# PROCESSOR.net
KiCad netlist of a schematic drawn in Altium Designer
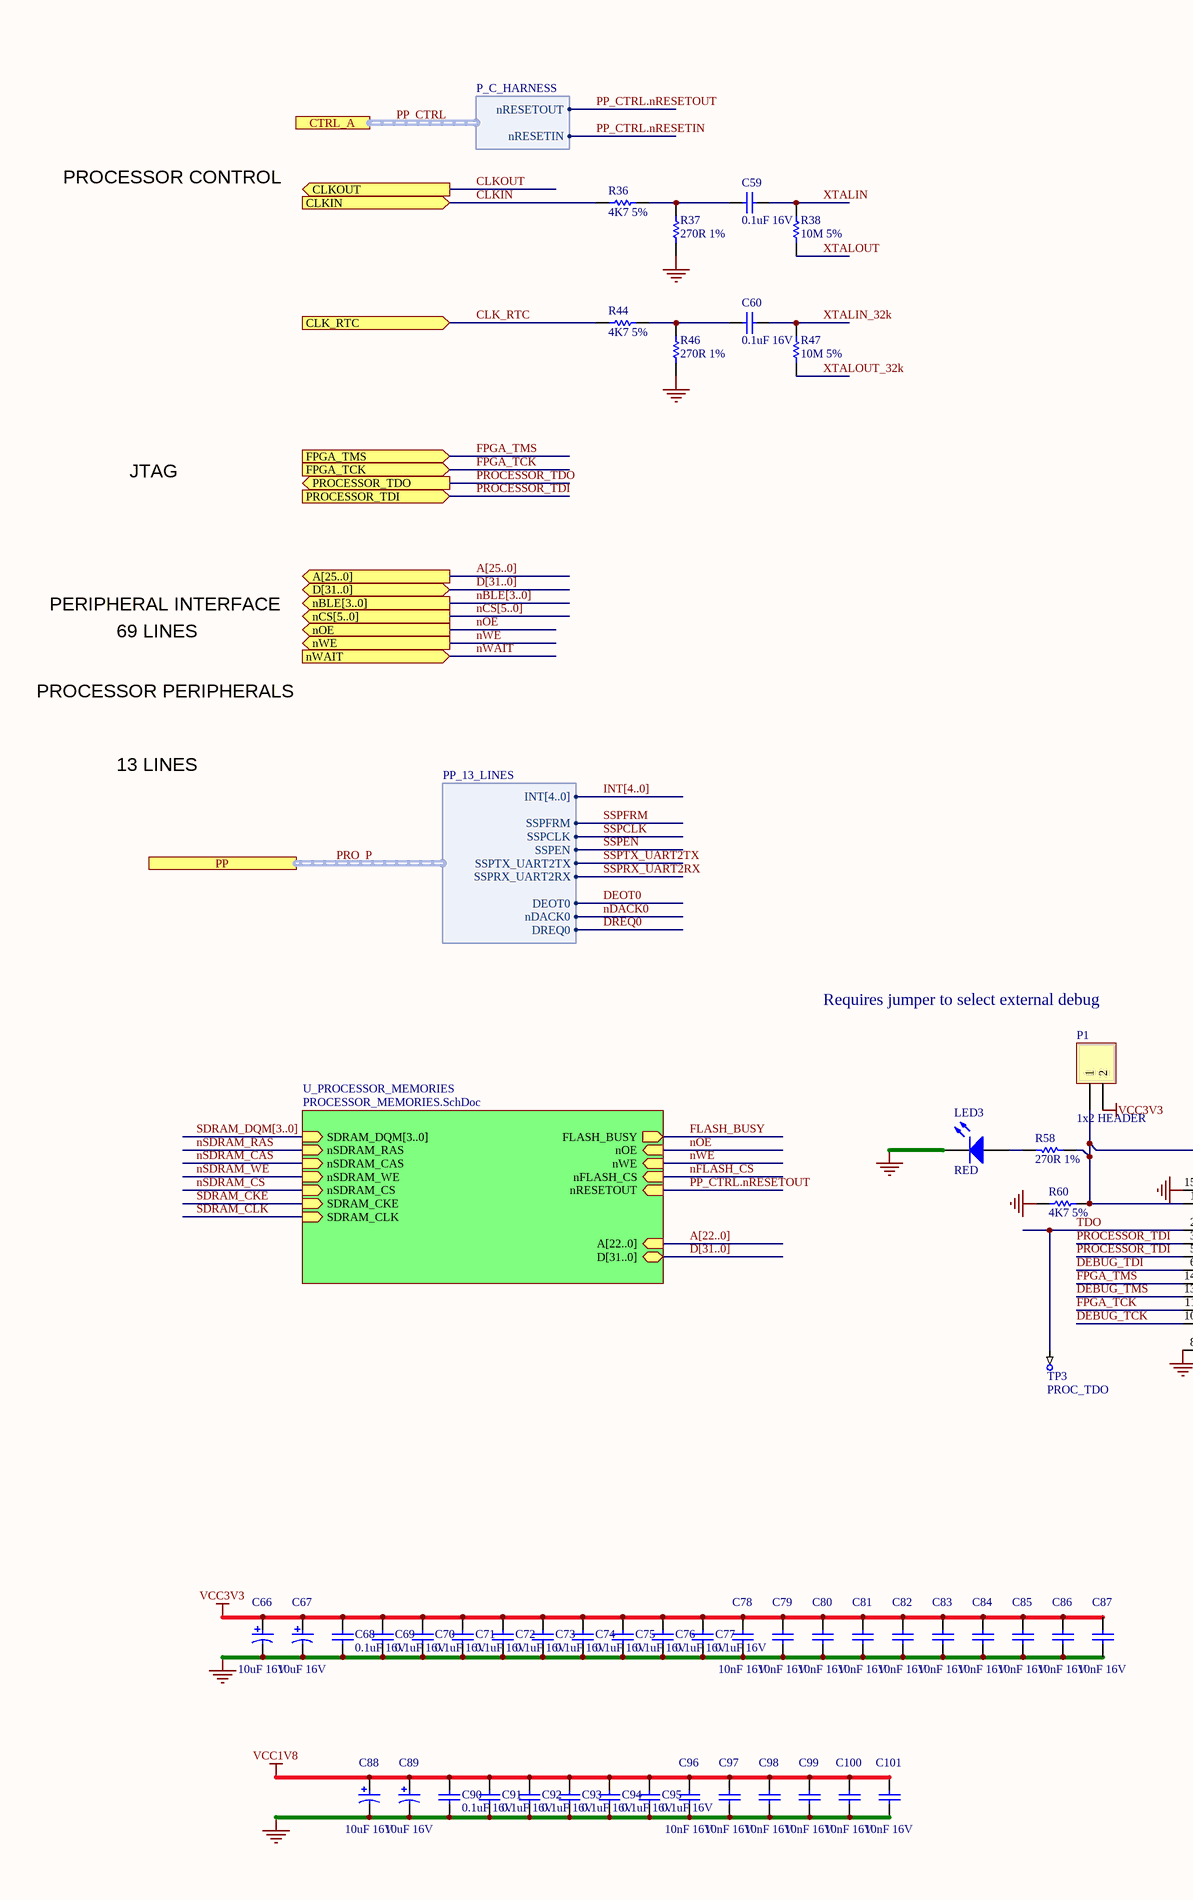
[diagram p0: PROCESSOR.SchDoc, left]
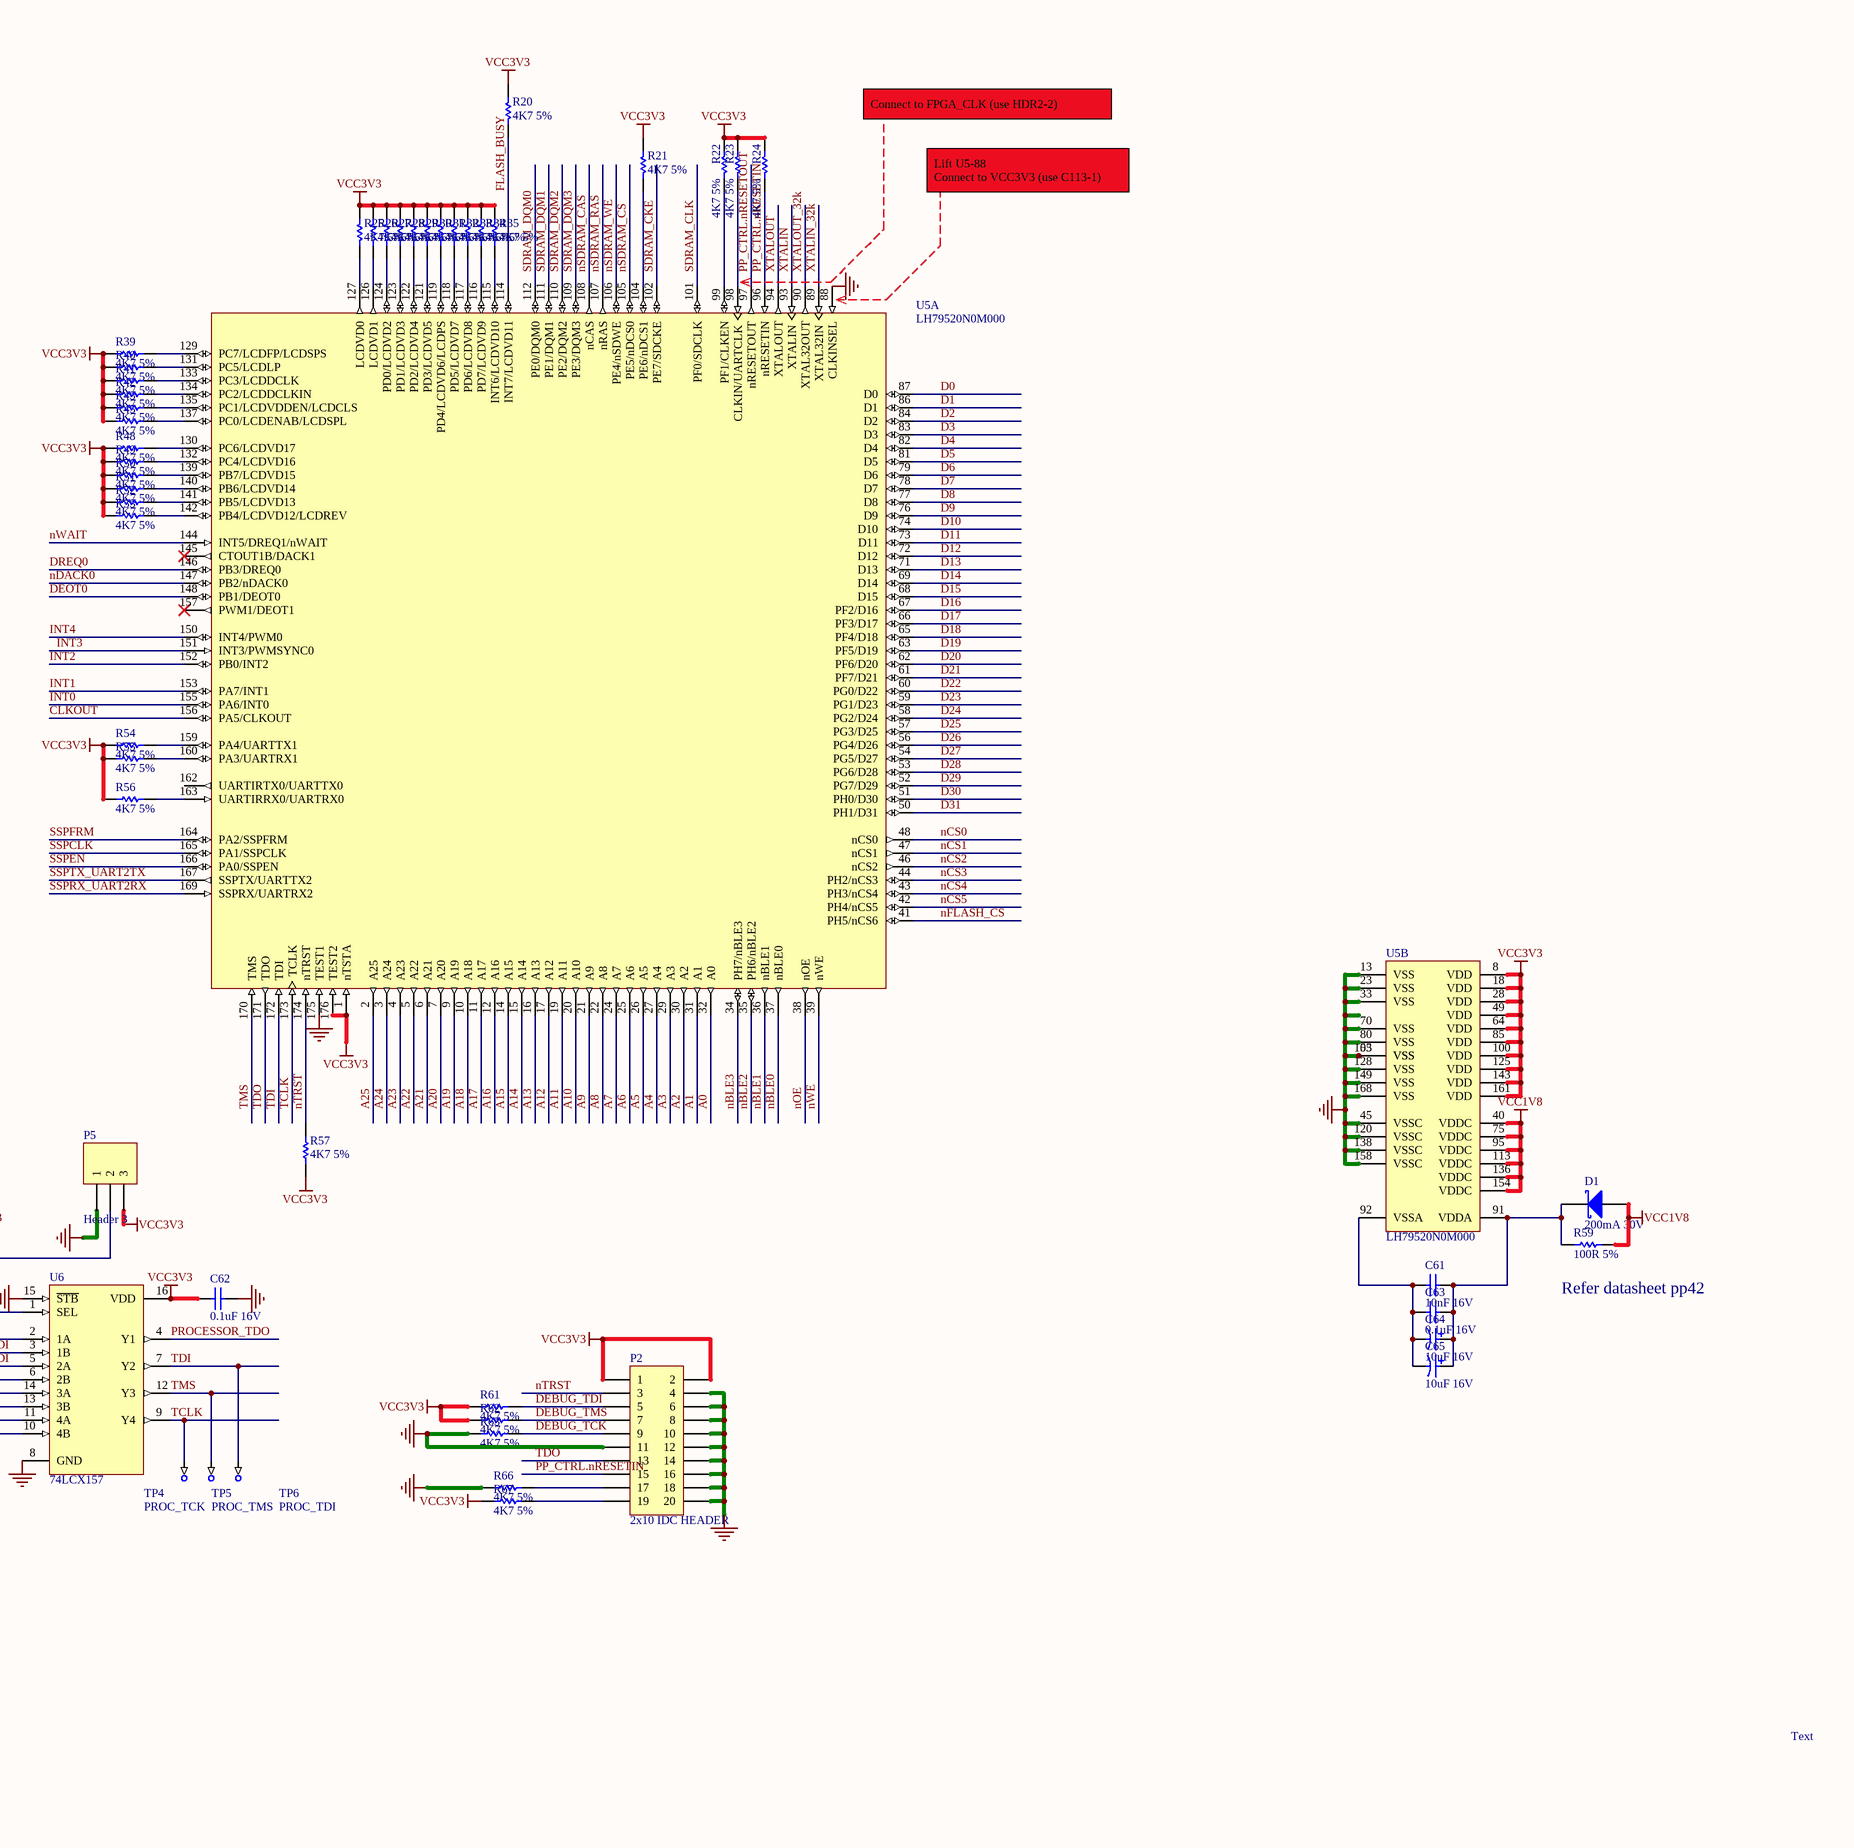
[diagram p1: PROCESSOR.SchDoc, right]

(export (version "E")
  (design (tool "Eeschema 10.0.6"))
  (components
    (comp (ref "C59")
      (value "0.1uF 16V")
      (footprint "CAPC1005")
      (description "Capacitor")
      (libsource (lib "Altium Design Library") (part "CAP-NP"))
    )
    (comp (ref "C60")
      (value "0.1uF 16V")
      (footprint "CAPC1005")
      (description "Capacitor")
      (libsource (lib "Altium Design Library") (part "CAP-NP"))
    )
    (comp (ref "C61")
      (value "10nF 16V")
      (footprint "CAPC1005")
      (description "Capacitor")
      (libsource (lib "Altium Design Library") (part "CAP-NP"))
    )
    (comp (ref "C62")
      (value "0.1uF 16V")
      (footprint "CAPC1005")
      (description "Capacitor")
      (libsource (lib "Altium Design Library") (part "CAP-NP"))
    )
    (comp (ref "C63")
      (value "0.1uF 16V")
      (footprint "CAPC1005")
      (description "Capacitor")
      (libsource (lib "Altium Design Library") (part "CAP-NP"))
    )
    (comp (ref "C64")
      (value "10uF 16V")
      (footprint "CAPC3528")
      (description "Polar Capacitor")
      (libsource (lib "Altium Design Library") (part "CAP-P"))
    )
    (comp (ref "C65")
      (value "10uF 16V")
      (footprint "CAPC3528")
      (description "Polar Capacitor")
      (libsource (lib "Altium Design Library") (part "CAP-P"))
    )
    (comp (ref "C66")
      (value "10uF 16V")
      (footprint "CAPC3528")
      (description "Polar Capacitor")
      (libsource (lib "Altium Design Library") (part "CAP-P"))
    )
    (comp (ref "C67")
      (value "10uF 16V")
      (footprint "CAPC3528")
      (description "Polar Capacitor")
      (libsource (lib "Altium Design Library") (part "CAP-P"))
    )
    (comp (ref "C68")
      (value "0.1uF 16V")
      (footprint "CAPC1005")
      (description "Capacitor")
      (libsource (lib "Altium Design Library") (part "CAP-NP"))
    )
    (comp (ref "C69")
      (value "0.1uF 16V")
      (footprint "CAPC1005")
      (description "Capacitor")
      (libsource (lib "Altium Design Library") (part "CAP-NP"))
    )
    (comp (ref "C70")
      (value "0.1uF 16V")
      (footprint "CAPC1005")
      (description "Capacitor")
      (libsource (lib "Altium Design Library") (part "CAP-NP"))
    )
    (comp (ref "C71")
      (value "0.1uF 16V")
      (footprint "CAPC1005")
      (description "Capacitor")
      (libsource (lib "Altium Design Library") (part "CAP-NP"))
    )
    (comp (ref "C72")
      (value "0.1uF 16V")
      (footprint "CAPC1005")
      (description "Capacitor")
      (libsource (lib "Altium Design Library") (part "CAP-NP"))
    )
    (comp (ref "C73")
      (value "0.1uF 16V")
      (footprint "CAPC1005")
      (description "Capacitor")
      (libsource (lib "Altium Design Library") (part "CAP-NP"))
    )
    (comp (ref "C74")
      (value "0.1uF 16V")
      (footprint "CAPC1005")
      (description "Capacitor")
      (libsource (lib "Altium Design Library") (part "CAP-NP"))
    )
    (comp (ref "C75")
      (value "0.1uF 16V")
      (footprint "CAPC1005")
      (description "Capacitor")
      (libsource (lib "Altium Design Library") (part "CAP-NP"))
    )
    (comp (ref "C76")
      (value "0.1uF 16V")
      (footprint "CAPC1005")
      (description "Capacitor")
      (libsource (lib "Altium Design Library") (part "CAP-NP"))
    )
    (comp (ref "C77")
      (value "0.1uF 16V")
      (footprint "CAPC1005")
      (description "Capacitor")
      (libsource (lib "Altium Design Library") (part "CAP-NP"))
    )
    (comp (ref "C78")
      (value "10nF 16V")
      (footprint "CAPC1005")
      (description "Capacitor")
      (libsource (lib "Altium Design Library") (part "CAP-NP"))
    )
    (comp (ref "C79")
      (value "10nF 16V")
      (footprint "CAPC1005")
      (description "Capacitor")
      (libsource (lib "Altium Design Library") (part "CAP-NP"))
    )
    (comp (ref "C80")
      (value "10nF 16V")
      (footprint "CAPC1005")
      (description "Capacitor")
      (libsource (lib "Altium Design Library") (part "CAP-NP"))
    )
    (comp (ref "C81")
      (value "10nF 16V")
      (footprint "CAPC1005")
      (description "Capacitor")
      (libsource (lib "Altium Design Library") (part "CAP-NP"))
    )
    (comp (ref "C82")
      (value "10nF 16V")
      (footprint "CAPC1005")
      (description "Capacitor")
      (libsource (lib "Altium Design Library") (part "CAP-NP"))
    )
    (comp (ref "C83")
      (value "10nF 16V")
      (footprint "CAPC1005")
      (description "Capacitor")
      (libsource (lib "Altium Design Library") (part "CAP-NP"))
    )
    (comp (ref "C84")
      (value "10nF 16V")
      (footprint "CAPC1005")
      (description "Capacitor")
      (libsource (lib "Altium Design Library") (part "CAP-NP"))
    )
    (comp (ref "C85")
      (value "10nF 16V")
      (footprint "CAPC1005")
      (description "Capacitor")
      (libsource (lib "Altium Design Library") (part "CAP-NP"))
    )
    (comp (ref "C86")
      (value "10nF 16V")
      (footprint "CAPC1005")
      (description "Capacitor")
      (libsource (lib "Altium Design Library") (part "CAP-NP"))
    )
    (comp (ref "C87")
      (value "10nF 16V")
      (footprint "CAPC1005")
      (description "Capacitor")
      (libsource (lib "Altium Design Library") (part "CAP-NP"))
    )
    (comp (ref "C88")
      (value "10uF 16V")
      (footprint "CAPC3528")
      (description "Polar Capacitor")
      (libsource (lib "Altium Design Library") (part "CAP-P"))
    )
    (comp (ref "C89")
      (value "10uF 16V")
      (footprint "CAPC3528")
      (description "Polar Capacitor")
      (libsource (lib "Altium Design Library") (part "CAP-P"))
    )
    (comp (ref "C90")
      (value "0.1uF 16V")
      (footprint "CAPC1005")
      (description "Capacitor")
      (libsource (lib "Altium Design Library") (part "CAP-NP"))
    )
    (comp (ref "C91")
      (value "0.1uF 16V")
      (footprint "CAPC1005")
      (description "Capacitor")
      (libsource (lib "Altium Design Library") (part "CAP-NP"))
    )
    (comp (ref "C92")
      (value "0.1uF 16V")
      (footprint "CAPC1005")
      (description "Capacitor")
      (libsource (lib "Altium Design Library") (part "CAP-NP"))
    )
    (comp (ref "C93")
      (value "0.1uF 16V")
      (footprint "CAPC1005")
      (description "Capacitor")
      (libsource (lib "Altium Design Library") (part "CAP-NP"))
    )
    (comp (ref "C94")
      (value "0.1uF 16V")
      (footprint "CAPC1005")
      (description "Capacitor")
      (libsource (lib "Altium Design Library") (part "CAP-NP"))
    )
    (comp (ref "C95")
      (value "0.1uF 16V")
      (footprint "CAPC1005")
      (description "Capacitor")
      (libsource (lib "Altium Design Library") (part "CAP-NP"))
    )
    (comp (ref "C96")
      (value "10nF 16V")
      (footprint "CAPC1005")
      (description "Capacitor")
      (libsource (lib "Altium Design Library") (part "CAP-NP"))
    )
    (comp (ref "C97")
      (value "10nF 16V")
      (footprint "CAPC1005")
      (description "Capacitor")
      (libsource (lib "Altium Design Library") (part "CAP-NP"))
    )
    (comp (ref "C98")
      (value "10nF 16V")
      (footprint "CAPC1005")
      (description "Capacitor")
      (libsource (lib "Altium Design Library") (part "CAP-NP"))
    )
    (comp (ref "C99")
      (value "10nF 16V")
      (footprint "CAPC1005")
      (description "Capacitor")
      (libsource (lib "Altium Design Library") (part "CAP-NP"))
    )
    (comp (ref "C100")
      (value "10nF 16V")
      (footprint "CAPC1005")
      (description "Capacitor")
      (libsource (lib "Altium Design Library") (part "CAP-NP"))
    )
    (comp (ref "C101")
      (value "10nF 16V")
      (footprint "CAPC1005")
      (description "Capacitor")
      (libsource (lib "Altium Design Library") (part "CAP-NP"))
    )
    (comp (ref "D1")
      (value "200mA 30V")
      (footprint "SOT95P230-3")
      (description "Schottky Barrier Double Diode")
      (libsource (lib "Altium Design Library") (part "DIO-SCHOTTKY-1S-SOT23"))
    )
    (comp (ref "LED3")
      (value "RED")
      (footprint "LED2013")
      (description "Typical GREEN SMD LED Agilent make")
      (libsource (lib "Altium Design Library") (part "DIO-LED-1S"))
    )
    (comp (ref "P1")
      (value "1x2 HEADER")
      (footprint "HDR1X2")
      (description "Header, 2-Pin")
      (libsource (lib "Altium Design Library") (part "CON-HDR-1x2-STR"))
    )
    (comp (ref "P2")
      (value "2x10 IDC HEADER")
      (footprint "IDC2.54-V20D")
      (description "10x2 IDC Male PCB Box Header")
      (libsource (lib "Altium Design Library") (part "CON-IDC-2x10-M-STR"))
    )
    (comp (ref "P5")
      (value "Header 3")
      (footprint "HDR1X3")
      (description "Header, 3-Pin")
      (fields (field (name "PUBLISHER") "Altium Limited"))
      (libsource (lib "Miscellaneous Connectors") (part "Header 3"))
    )
    (comp (ref "R20")
      (value "4K7 5%")
      (footprint "RESC1005")
      (description "Resistor")
      (libsource (lib "Altium Design Library") (part "RES"))
    )
    (comp (ref "R21")
      (value "4K7 5%")
      (footprint "RESC1005")
      (description "Resistor")
      (libsource (lib "Altium Design Library") (part "RES"))
    )
    (comp (ref "R22")
      (value "4K7 5%")
      (footprint "RESC1005")
      (description "Resistor")
      (libsource (lib "Altium Design Library") (part "RES"))
    )
    (comp (ref "R23")
      (value "4K7 5%")
      (footprint "RESC1005")
      (description "Resistor")
      (libsource (lib "Altium Design Library") (part "RES"))
    )
    (comp (ref "R24")
      (value "4K7 5%")
      (footprint "RESC1005")
      (description "Resistor")
      (libsource (lib "Altium Design Library") (part "RES"))
    )
    (comp (ref "R25")
      (value "4K7 5%")
      (footprint "RESC1005")
      (description "Resistor")
      (libsource (lib "Altium Design Library") (part "RES"))
    )
    (comp (ref "R26")
      (value "4K7 5%")
      (footprint "RESC1005")
      (description "Resistor")
      (libsource (lib "Altium Design Library") (part "RES"))
    )
    (comp (ref "R27")
      (value "4K7 5%")
      (footprint "RESC1005")
      (description "Resistor")
      (libsource (lib "Altium Design Library") (part "RES"))
    )
    (comp (ref "R28")
      (value "4K7 5%")
      (footprint "RESC1005")
      (description "Resistor")
      (libsource (lib "Altium Design Library") (part "RES"))
    )
    (comp (ref "R29")
      (value "4K7 5%")
      (footprint "RESC1005")
      (description "Resistor")
      (libsource (lib "Altium Design Library") (part "RES"))
    )
    (comp (ref "R30")
      (value "4K7 5%")
      (footprint "RESC1005")
      (description "Resistor")
      (libsource (lib "Altium Design Library") (part "RES"))
    )
    (comp (ref "R31")
      (value "4K7 5%")
      (footprint "RESC1005")
      (description "Resistor")
      (libsource (lib "Altium Design Library") (part "RES"))
    )
    (comp (ref "R32")
      (value "4K7 5%")
      (footprint "RESC1005")
      (description "Resistor")
      (libsource (lib "Altium Design Library") (part "RES"))
    )
    (comp (ref "R33")
      (value "4K7 5%")
      (footprint "RESC1005")
      (description "Resistor")
      (libsource (lib "Altium Design Library") (part "RES"))
    )
    (comp (ref "R34")
      (value "4K7 5%")
      (footprint "RESC1005")
      (description "Resistor")
      (libsource (lib "Altium Design Library") (part "RES"))
    )
    (comp (ref "R35")
      (value "4K7 5%")
      (footprint "RESC1005")
      (description "Resistor")
      (libsource (lib "Altium Design Library") (part "RES"))
    )
    (comp (ref "R36")
      (value "4K7 5%")
      (footprint "RESC1005")
      (description "Resistor")
      (libsource (lib "Altium Design Library") (part "RES"))
    )
    (comp (ref "R37")
      (value "270R 1%")
      (footprint "RESC2012")
      (description "Resistor")
      (libsource (lib "Altium Design Library") (part "RES"))
    )
    (comp (ref "R38")
      (value "10M 5%")
      (footprint "RESC2012")
      (description "Resistor")
      (libsource (lib "Altium Design Library") (part "RES"))
    )
    (comp (ref "R39")
      (value "4K7 5%")
      (footprint "RESC1005")
      (description "Resistor")
      (libsource (lib "Altium Design Library") (part "RES"))
    )
    (comp (ref "R40")
      (value "4K7 5%")
      (footprint "RESC1005")
      (description "Resistor")
      (libsource (lib "Altium Design Library") (part "RES"))
    )
    (comp (ref "R41")
      (value "4K7 5%")
      (footprint "RESC1005")
      (description "Resistor")
      (libsource (lib "Altium Design Library") (part "RES"))
    )
    (comp (ref "R42")
      (value "4K7 5%")
      (footprint "RESC1005")
      (description "Resistor")
      (libsource (lib "Altium Design Library") (part "RES"))
    )
    (comp (ref "R43")
      (value "4K7 5%")
      (footprint "RESC1005")
      (description "Resistor")
      (libsource (lib "Altium Design Library") (part "RES"))
    )
    (comp (ref "R44")
      (value "4K7 5%")
      (footprint "RESC1005")
      (description "Resistor")
      (libsource (lib "Altium Design Library") (part "RES"))
    )
    (comp (ref "R45")
      (value "4K7 5%")
      (footprint "RESC1005")
      (description "Resistor")
      (libsource (lib "Altium Design Library") (part "RES"))
    )
    (comp (ref "R46")
      (value "270R 1%")
      (footprint "RESC2012")
      (description "Resistor")
      (libsource (lib "Altium Design Library") (part "RES"))
    )
    (comp (ref "R47")
      (value "10M 5%")
      (footprint "RESC2012")
      (description "Resistor")
      (libsource (lib "Altium Design Library") (part "RES"))
    )
    (comp (ref "R48")
      (value "4K7 5%")
      (footprint "RESC1005")
      (description "Resistor")
      (libsource (lib "Altium Design Library") (part "RES"))
    )
    (comp (ref "R49")
      (value "4K7 5%")
      (footprint "RESC1005")
      (description "Resistor")
      (libsource (lib "Altium Design Library") (part "RES"))
    )
    (comp (ref "R50")
      (value "4K7 5%")
      (footprint "RESC1005")
      (description "Resistor")
      (libsource (lib "Altium Design Library") (part "RES"))
    )
    (comp (ref "R51")
      (value "4K7 5%")
      (footprint "RESC1005")
      (description "Resistor")
      (libsource (lib "Altium Design Library") (part "RES"))
    )
    (comp (ref "R52")
      (value "4K7 5%")
      (footprint "RESC1005")
      (description "Resistor")
      (libsource (lib "Altium Design Library") (part "RES"))
    )
    (comp (ref "R53")
      (value "4K7 5%")
      (footprint "RESC1005")
      (description "Resistor")
      (libsource (lib "Altium Design Library") (part "RES"))
    )
    (comp (ref "R54")
      (value "4K7 5%")
      (footprint "RESC1005")
      (description "Resistor")
      (libsource (lib "Altium Design Library") (part "RES"))
    )
    (comp (ref "R55")
      (value "4K7 5%")
      (footprint "RESC1005")
      (description "Resistor")
      (libsource (lib "Altium Design Library") (part "RES"))
    )
    (comp (ref "R56")
      (value "4K7 5%")
      (footprint "RESC1005")
      (description "Resistor")
      (libsource (lib "Altium Design Library") (part "RES"))
    )
    (comp (ref "R57")
      (value "4K7 5%")
      (footprint "RESC1005")
      (description "Resistor")
      (libsource (lib "Altium Design Library") (part "RES"))
    )
    (comp (ref "R58")
      (value "270R 1%")
      (footprint "RESC2012")
      (description "Resistor")
      (libsource (lib "Altium Design Library") (part "RES"))
    )
    (comp (ref "R59")
      (value "100R 5%")
      (footprint "RESC2012")
      (description "Resistor")
      (libsource (lib "Altium Design Library") (part "RES"))
    )
    (comp (ref "R60")
      (value "4K7 5%")
      (footprint "RESC1005")
      (description "Resistor")
      (libsource (lib "Altium Design Library") (part "RES"))
    )
    (comp (ref "R61")
      (value "4K7 5%")
      (footprint "RESC1005")
      (description "Resistor")
      (libsource (lib "Altium Design Library") (part "RES"))
    )
    (comp (ref "R62")
      (value "4K7 5%")
      (footprint "RESC1005")
      (description "Resistor")
      (libsource (lib "Altium Design Library") (part "RES"))
    )
    (comp (ref "R63")
      (value "4K7 5%")
      (footprint "RESC1005")
      (description "Resistor")
      (libsource (lib "Altium Design Library") (part "RES"))
    )
    (comp (ref "R66")
      (value "4K7 5%")
      (footprint "RESC1005")
      (description "Resistor")
      (libsource (lib "Altium Design Library") (part "RES"))
    )
    (comp (ref "R67")
      (value "4K7 5%")
      (footprint "RESC1005")
      (description "Resistor")
      (libsource (lib "Altium Design Library") (part "RES"))
    )
    (comp (ref "TP3")
      (value "PROC_TDO")
      (footprint "TestPin")
      (libsource (lib "Altium Design Library") (part "TestPin"))
    )
    (comp (ref "TP4")
      (value "PROC_TCK")
      (footprint "TestPin")
      (libsource (lib "Altium Design Library") (part "TestPin"))
    )
    (comp (ref "TP5")
      (value "PROC_TMS")
      (footprint "TestPin")
      (libsource (lib "Altium Design Library") (part "TestPin"))
    )
    (comp (ref "TP6")
      (value "PROC_TDI")
      (footprint "TestPin")
      (libsource (lib "Altium Design Library") (part "TestPin"))
    )
    (comp (ref "U5")
      (value "LH79520N0M000")
      (footprint "QFP40P2000X2000-176")
      (libsource (lib "Altium Design Library") (part "LH79520N0M000"))
    )
    (comp (ref "U6")
      (value "74LCX157")
      (footprint "TSOP65P638-16")
      (description "Quad 2-Input Multiplexer")
      (libsource (lib "Altium Design Library") (part "74LCX157-TSOP16"))
    )
  )
  (nets
    (net (code "3") (name "/A0") (class "Default")
      (node (ref "U5") (pin "32") (pinfunction "A0_32") (pintype "output"))
    )
    (net (code "4") (name "/A1") (class "Default")
      (node (ref "U5") (pin "31") (pinfunction "A1_31") (pintype "output"))
    )
    (net (code "5") (name "/A2") (class "Default")
      (node (ref "U5") (pin "30") (pinfunction "A2_30") (pintype "output"))
    )
    (net (code "6") (name "/A3") (class "Default")
      (node (ref "U5") (pin "29") (pinfunction "A3_29") (pintype "output"))
    )
    (net (code "7") (name "/A4") (class "Default")
      (node (ref "U5") (pin "27") (pinfunction "A4_27") (pintype "output"))
    )
    (net (code "8") (name "/A5") (class "Default")
      (node (ref "U5") (pin "26") (pinfunction "A5_26") (pintype "output"))
    )
    (net (code "9") (name "/A6") (class "Default")
      (node (ref "U5") (pin "25") (pinfunction "A6_25") (pintype "output"))
    )
    (net (code "10") (name "/A7") (class "Default")
      (node (ref "U5") (pin "24") (pinfunction "A7_24") (pintype "output"))
    )
    (net (code "11") (name "/A8") (class "Default")
      (node (ref "U5") (pin "22") (pinfunction "A8_22") (pintype "output"))
    )
    (net (code "12") (name "/A9") (class "Default")
      (node (ref "U5") (pin "21") (pinfunction "A9_21") (pintype "output"))
    )
    (net (code "13") (name "/A10") (class "Default")
      (node (ref "U5") (pin "20") (pinfunction "A10_20") (pintype "output"))
    )
    (net (code "14") (name "/A11") (class "Default")
      (node (ref "U5") (pin "19") (pinfunction "A11_19") (pintype "output"))
    )
    (net (code "15") (name "/A12") (class "Default")
      (node (ref "U5") (pin "17") (pinfunction "A12_17") (pintype "output"))
    )
    (net (code "16") (name "/A13") (class "Default")
      (node (ref "U5") (pin "16") (pinfunction "A13_16") (pintype "output"))
    )
    (net (code "17") (name "/A14") (class "Default")
      (node (ref "U5") (pin "15") (pinfunction "A14_15") (pintype "output"))
    )
    (net (code "18") (name "/A15") (class "Default")
      (node (ref "U5") (pin "14") (pinfunction "A15_14") (pintype "output"))
    )
    (net (code "19") (name "/A16") (class "Default")
      (node (ref "U5") (pin "12") (pinfunction "A16_12") (pintype "output"))
    )
    (net (code "20") (name "/A17") (class "Default")
      (node (ref "U5") (pin "11") (pinfunction "A17_11") (pintype "output"))
    )
    (net (code "21") (name "/A18") (class "Default")
      (node (ref "U5") (pin "10") (pinfunction "A18_10") (pintype "output"))
    )
    (net (code "22") (name "/A19") (class "Default")
      (node (ref "U5") (pin "9") (pinfunction "A19_9") (pintype "output"))
    )
    (net (code "23") (name "/A20") (class "Default")
      (node (ref "U5") (pin "7") (pinfunction "A20_7") (pintype "output"))
    )
    (net (code "24") (name "/A21") (class "Default")
      (node (ref "U5") (pin "6") (pinfunction "A21_6") (pintype "output"))
    )
    (net (code "25") (name "/A22") (class "Default")
      (node (ref "U5") (pin "5") (pinfunction "A22_5") (pintype "output"))
    )
    (net (code "26") (name "/A23") (class "Default")
      (node (ref "U5") (pin "4") (pinfunction "A23_4") (pintype "output"))
    )
    (net (code "27") (name "/A24") (class "Default")
      (node (ref "U5") (pin "3") (pinfunction "A24_3") (pintype "output"))
    )
    (net (code "28") (name "/A25") (class "Default")
      (node (ref "U5") (pin "2") (pinfunction "A25_2") (pintype "output"))
    )
    (net (code "31") (name "/CLKIN") (class "Default")
      (node (ref "R36") (pin "2") (pinfunction "2_2") (pintype "passive"))
    )
    (net (code "32") (name "/CLKOUT") (class "Default")
      (node (ref "U5") (pin "156") (pinfunction "PA5/CLKOUT_156") (pintype "bidirectional"))
    )
    (net (code "33") (name "/CLK_RTC") (class "Default")
      (node (ref "R44") (pin "2") (pinfunction "2_2") (pintype "passive"))
    )
    (net (code "34") (name "/D0") (class "Default")
      (node (ref "U5") (pin "87") (pinfunction "D0_87") (pintype "bidirectional"))
    )
    (net (code "35") (name "/D1") (class "Default")
      (node (ref "U5") (pin "86") (pinfunction "D1_86") (pintype "bidirectional"))
    )
    (net (code "36") (name "/D2") (class "Default")
      (node (ref "U5") (pin "84") (pinfunction "D2_84") (pintype "bidirectional"))
    )
    (net (code "37") (name "/D3") (class "Default")
      (node (ref "U5") (pin "83") (pinfunction "D3_83") (pintype "bidirectional"))
    )
    (net (code "38") (name "/D4") (class "Default")
      (node (ref "U5") (pin "82") (pinfunction "D4_82") (pintype "bidirectional"))
    )
    (net (code "39") (name "/D5") (class "Default")
      (node (ref "U5") (pin "81") (pinfunction "D5_81") (pintype "bidirectional"))
    )
    (net (code "40") (name "/D6") (class "Default")
      (node (ref "U5") (pin "79") (pinfunction "D6_79") (pintype "bidirectional"))
    )
    (net (code "41") (name "/D7") (class "Default")
      (node (ref "U5") (pin "78") (pinfunction "D7_78") (pintype "bidirectional"))
    )
    (net (code "42") (name "/D8") (class "Default")
      (node (ref "U5") (pin "77") (pinfunction "D8_77") (pintype "bidirectional"))
    )
    (net (code "43") (name "/D9") (class "Default")
      (node (ref "U5") (pin "76") (pinfunction "D9_76") (pintype "bidirectional"))
    )
    (net (code "44") (name "/D10") (class "Default")
      (node (ref "U5") (pin "74") (pinfunction "D10_74") (pintype "bidirectional"))
    )
    (net (code "45") (name "/D11") (class "Default")
      (node (ref "U5") (pin "73") (pinfunction "D11_73") (pintype "bidirectional"))
    )
    (net (code "46") (name "/D12") (class "Default")
      (node (ref "U5") (pin "72") (pinfunction "D12_72") (pintype "bidirectional"))
    )
    (net (code "47") (name "/D13") (class "Default")
      (node (ref "U5") (pin "71") (pinfunction "D13_71") (pintype "bidirectional"))
    )
    (net (code "48") (name "/D14") (class "Default")
      (node (ref "U5") (pin "69") (pinfunction "D14_69") (pintype "bidirectional"))
    )
    (net (code "49") (name "/D15") (class "Default")
      (node (ref "U5") (pin "68") (pinfunction "D15_68") (pintype "bidirectional"))
    )
    (net (code "50") (name "/D16") (class "Default")
      (node (ref "U5") (pin "67") (pinfunction "PF2/D16_67") (pintype "bidirectional"))
    )
    (net (code "51") (name "/D17") (class "Default")
      (node (ref "U5") (pin "66") (pinfunction "PF3/D17_66") (pintype "bidirectional"))
    )
    (net (code "52") (name "/D18") (class "Default")
      (node (ref "U5") (pin "65") (pinfunction "PF4/D18_65") (pintype "bidirectional"))
    )
    (net (code "53") (name "/D19") (class "Default")
      (node (ref "U5") (pin "63") (pinfunction "PF5/D19_63") (pintype "bidirectional"))
    )
    (net (code "54") (name "/D20") (class "Default")
      (node (ref "U5") (pin "62") (pinfunction "PF6/D20_62") (pintype "bidirectional"))
    )
    (net (code "55") (name "/D21") (class "Default")
      (node (ref "U5") (pin "61") (pinfunction "PF7/D21_61") (pintype "bidirectional"))
    )
    (net (code "56") (name "/D22") (class "Default")
      (node (ref "U5") (pin "60") (pinfunction "PG0/D22_60") (pintype "bidirectional"))
    )
    (net (code "57") (name "/D23") (class "Default")
      (node (ref "U5") (pin "59") (pinfunction "PG1/D23_59") (pintype "bidirectional"))
    )
    (net (code "58") (name "/D24") (class "Default")
      (node (ref "U5") (pin "58") (pinfunction "PG2/D24_58") (pintype "bidirectional"))
    )
    (net (code "59") (name "/D25") (class "Default")
      (node (ref "U5") (pin "57") (pinfunction "PG3/D25_57") (pintype "bidirectional"))
    )
    (net (code "60") (name "/D26") (class "Default")
      (node (ref "U5") (pin "56") (pinfunction "PG4/D26_56") (pintype "bidirectional"))
    )
    (net (code "61") (name "/D27") (class "Default")
      (node (ref "U5") (pin "54") (pinfunction "PG5/D27_54") (pintype "bidirectional"))
    )
    (net (code "62") (name "/D28") (class "Default")
      (node (ref "U5") (pin "53") (pinfunction "PG6/D28_53") (pintype "bidirectional"))
    )
    (net (code "63") (name "/D29") (class "Default")
      (node (ref "U5") (pin "52") (pinfunction "PG7/D29_52") (pintype "bidirectional"))
    )
    (net (code "64") (name "/D30") (class "Default")
      (node (ref "U5") (pin "51") (pinfunction "PH0/D30_51") (pintype "bidirectional"))
    )
    (net (code "65") (name "/D31") (class "Default")
      (node (ref "U5") (pin "50") (pinfunction "PH1/D31_50") (pintype "bidirectional"))
    )
    (net (code "66") (name "/DEBUG_TCK") (class "Default")
      (node (ref "P2") (pin "9") (pinfunction "9_9") (pintype "passive"))
      (node (ref "R63") (pin "2") (pinfunction "2_2") (pintype "passive"))
      (node (ref "U6") (pin "10") (pinfunction "4B_10") (pintype "input"))
    )
    (net (code "67") (name "/DEBUG_TDI") (class "Default")
      (node (ref "P2") (pin "5") (pinfunction "5_5") (pintype "passive"))
      (node (ref "R61") (pin "2") (pinfunction "2_2") (pintype "passive"))
      (node (ref "U6") (pin "6") (pinfunction "2B_6") (pintype "input"))
    )
    (net (code "68") (name "/DEBUG_TMS") (class "Default")
      (node (ref "P2") (pin "7") (pinfunction "7_7") (pintype "passive"))
      (node (ref "R62") (pin "2") (pinfunction "2_2") (pintype "passive"))
      (node (ref "U6") (pin "13") (pinfunction "3B_13") (pintype "input"))
    )
    (net (code "69") (name "/DEOT0") (class "Default")
      (node (ref "U5") (pin "148") (pinfunction "PB1/DEOT0_148") (pintype "bidirectional"))
    )
    (net (code "70") (name "/DREQ0") (class "Default")
      (node (ref "U5") (pin "146") (pinfunction "PB3/DREQ0_146") (pintype "bidirectional"))
    )
    (net (code "72") (name "/FLASH_BUSY") (class "Default")
      (node (ref "R20") (pin "1") (pinfunction "1_1") (pintype "passive"))
      (node (ref "U5") (pin "114") (pinfunction "INT7/LCDVD11_114") (pintype "bidirectional"))
    )
    (net (code "73") (name "/FPGA_TCK") (class "Default")
      (node (ref "U6") (pin "11") (pinfunction "4A_11") (pintype "input"))
    )
    (net (code "74") (name "/FPGA_TMS") (class "Default")
      (node (ref "U6") (pin "14") (pinfunction "3A_14") (pintype "input"))
    )
    (net (code "75") (name "/INT0") (class "Default")
      (node (ref "U5") (pin "155") (pinfunction "PA6/INT0_155") (pintype "bidirectional"))
    )
    (net (code "76") (name "/INT1") (class "Default")
      (node (ref "U5") (pin "153") (pinfunction "PA7/INT1_153") (pintype "bidirectional"))
    )
    (net (code "77") (name "/INT2") (class "Default")
      (node (ref "U5") (pin "152") (pinfunction "PB0/INT2_152") (pintype "bidirectional"))
    )
    (net (code "78") (name "/INT3") (class "Default")
      (node (ref "U5") (pin "151") (pinfunction "INT3/PWMSYNC0_151") (pintype "input"))
    )
    (net (code "79") (name "/INT4") (class "Default")
      (node (ref "U5") (pin "150") (pinfunction "INT4/PWM0_150") (pintype "bidirectional"))
    )
    (net (code "80") (name "/PP_CTRL.nRESETIN") (class "Default")
      (node (ref "P2") (pin "15") (pinfunction "15_15") (pintype "passive"))
      (node (ref "R24") (pin "1") (pinfunction "1_1") (pintype "passive"))
      (node (ref "U5") (pin "96") (pinfunction "nRESETIN_96") (pintype "input"))
    )
    (net (code "81") (name "/PP_CTRL.nRESETOUT") (class "Default")
      (node (ref "U5") (pin "97") (pinfunction "nRESETOUT_97") (pintype "output"))
    )
    (net (code "83") (name "/PROCESSOR_TDI") (class "Default")
      (node (ref "U6") (pin "3") (pinfunction "1B_3") (pintype "input"))
      (node (ref "U6") (pin "5") (pinfunction "2A_5") (pintype "input"))
    )
    (net (code "84") (name "/PROCESSOR_TDO") (class "Default")
      (node (ref "U6") (pin "4") (pinfunction "Y1_4") (pintype "output"))
    )
    (net (code "85") (name "/SDRAM_CKE") (class "Default")
      (node (ref "U5") (pin "102") (pinfunction "PE7/SDCKE_102") (pintype "bidirectional"))
    )
    (net (code "86") (name "/SDRAM_CLK") (class "Default")
      (node (ref "U5") (pin "101") (pinfunction "PF0/SDCLK_101") (pintype "bidirectional"))
    )
    (net (code "87") (name "/SDRAM_DQM0") (class "Default")
      (node (ref "U5") (pin "112") (pinfunction "PE0/DQM0_112") (pintype "bidirectional"))
    )
    (net (code "88") (name "/SDRAM_DQM1") (class "Default")
      (node (ref "U5") (pin "111") (pinfunction "PE1/DQM1_111") (pintype "bidirectional"))
    )
    (net (code "89") (name "/SDRAM_DQM2") (class "Default")
      (node (ref "U5") (pin "110") (pinfunction "PE2/DQM2_110") (pintype "bidirectional"))
    )
    (net (code "90") (name "/SDRAM_DQM3") (class "Default")
      (node (ref "U5") (pin "109") (pinfunction "PE3/DQM3_109") (pintype "bidirectional"))
    )
    (net (code "92") (name "/SSPCLK") (class "Default")
      (node (ref "U5") (pin "165") (pinfunction "PA1/SSPCLK_165") (pintype "bidirectional"))
    )
    (net (code "93") (name "/SSPEN") (class "Default")
      (node (ref "U5") (pin "166") (pinfunction "PA0/SSPEN_166") (pintype "bidirectional"))
    )
    (net (code "94") (name "/SSPFRM") (class "Default")
      (node (ref "U5") (pin "164") (pinfunction "PA2/SSPFRM_164") (pintype "bidirectional"))
    )
    (net (code "95") (name "/SSPRX_UART2RX") (class "Default")
      (node (ref "U5") (pin "169") (pinfunction "SSPRX/UARTRX2_169") (pintype "input"))
    )
    (net (code "96") (name "/SSPTX_UART2TX") (class "Default")
      (node (ref "U5") (pin "167") (pinfunction "SSPTX/UARTTX2_167") (pintype "output"))
    )
    (net (code "97") (name "/TCLK") (class "Default")
      (node (ref "TP4") (pin "1") (pinfunction "1_1") (pintype "input"))
      (node (ref "U5") (pin "173") (pinfunction "TCLK_173") (pintype "input"))
      (node (ref "U6") (pin "9") (pinfunction "Y4_9") (pintype "output"))
    )
    (net (code "98") (name "/TDI") (class "Default")
      (node (ref "TP6") (pin "1") (pinfunction "1_1") (pintype "input"))
      (node (ref "U5") (pin "172") (pinfunction "TDI_172") (pintype "input"))
      (node (ref "U6") (pin "7") (pinfunction "Y2_7") (pintype "output"))
    )
    (net (code "99") (name "/TDO") (class "Default")
      (node (ref "P2") (pin "13") (pinfunction "13_13") (pintype "passive"))
      (node (ref "TP3") (pin "1") (pinfunction "1_1") (pintype "input"))
      (node (ref "U5") (pin "171") (pinfunction "TDO_171") (pintype "output"))
      (node (ref "U6") (pin "2") (pinfunction "1A_2") (pintype "input"))
    )
    (net (code "100") (name "/TMS") (class "Default")
      (node (ref "TP5") (pin "1") (pinfunction "1_1") (pintype "input"))
      (node (ref "U5") (pin "170") (pinfunction "TMS_170") (pintype "input"))
      (node (ref "U6") (pin "12") (pinfunction "Y3_12") (pintype "output"))
    )
    (net (code "101") (name "/XTALIN") (class "Default")
      (node (ref "C59") (pin "2") (pinfunction "2_2") (pintype "passive"))
      (node (ref "R38") (pin "1") (pinfunction "1_1") (pintype "passive"))
      (node (ref "U5") (pin "93") (pinfunction "XTALIN_93") (pintype "input"))
    )
    (net (code "102") (name "/XTALIN_32k") (class "Default")
      (node (ref "C60") (pin "2") (pinfunction "2_2") (pintype "passive"))
      (node (ref "R47") (pin "1") (pinfunction "1_1") (pintype "passive"))
      (node (ref "U5") (pin "89") (pinfunction "XTAL32IN_89") (pintype "input"))
    )
    (net (code "103") (name "/XTALOUT") (class "Default")
      (node (ref "R38") (pin "2") (pinfunction "2_2") (pintype "passive"))
      (node (ref "U5") (pin "94") (pinfunction "XTALOUT_94") (pintype "output"))
    )
    (net (code "104") (name "/XTALOUT_32k") (class "Default")
      (node (ref "R47") (pin "2") (pinfunction "2_2") (pintype "passive"))
      (node (ref "U5") (pin "90") (pinfunction "XTAL32OUT_90") (pintype "output"))
    )
    (net (code "105") (name "/nBLE0") (class "Default")
      (node (ref "U5") (pin "37") (pinfunction "nBLE0_37") (pintype "output"))
    )
    (net (code "106") (name "/nBLE1") (class "Default")
      (node (ref "U5") (pin "36") (pinfunction "nBLE1_36") (pintype "output"))
    )
    (net (code "107") (name "/nBLE2") (class "Default")
      (node (ref "U5") (pin "35") (pinfunction "PH6/nBLE2_35") (pintype "bidirectional"))
    )
    (net (code "108") (name "/nBLE3") (class "Default")
      (node (ref "U5") (pin "34") (pinfunction "PH7/nBLE3_34") (pintype "bidirectional"))
    )
    (net (code "110") (name "/nCS0") (class "Default")
      (node (ref "U5") (pin "48") (pinfunction "nCS0_48") (pintype "output"))
    )
    (net (code "111") (name "/nCS1") (class "Default")
      (node (ref "U5") (pin "47") (pinfunction "nCS1_47") (pintype "output"))
    )
    (net (code "112") (name "/nCS2") (class "Default")
      (node (ref "U5") (pin "46") (pinfunction "nCS2_46") (pintype "output"))
    )
    (net (code "113") (name "/nCS3") (class "Default")
      (node (ref "U5") (pin "44") (pinfunction "PH2/nCS3_44") (pintype "bidirectional"))
    )
    (net (code "114") (name "/nCS4") (class "Default")
      (node (ref "U5") (pin "43") (pinfunction "PH3/nCS4_43") (pintype "bidirectional"))
    )
    (net (code "115") (name "/nCS5") (class "Default")
      (node (ref "U5") (pin "42") (pinfunction "PH4/nCS5_42") (pintype "bidirectional"))
    )
    (net (code "117") (name "/nDACK0") (class "Default")
      (node (ref "U5") (pin "147") (pinfunction "PB2/nDACK0_147") (pintype "bidirectional"))
    )
    (net (code "118") (name "/nFLASH_CS") (class "Default")
      (node (ref "U5") (pin "41") (pinfunction "PH5/nCS6_41") (pintype "bidirectional"))
    )
    (net (code "119") (name "/nOE") (class "Default")
      (node (ref "U5") (pin "38") (pinfunction "nOE_38") (pintype "output"))
    )
    (net (code "120") (name "/nSDRAM_CAS") (class "Default")
      (node (ref "U5") (pin "108") (pinfunction "nCAS_108") (pintype "output"))
    )
    (net (code "121") (name "/nSDRAM_CS") (class "Default")
      (node (ref "U5") (pin "105") (pinfunction "PE5/nDCS0_105") (pintype "bidirectional"))
    )
    (net (code "122") (name "/nSDRAM_RAS") (class "Default")
      (node (ref "U5") (pin "107") (pinfunction "nRAS_107") (pintype "output"))
    )
    (net (code "123") (name "/nSDRAM_WE") (class "Default")
      (node (ref "U5") (pin "106") (pinfunction "PE4/nSDWE_106") (pintype "bidirectional"))
    )
    (net (code "124") (name "/nTRST") (class "Default")
      (node (ref "P2") (pin "3") (pinfunction "3_3") (pintype "passive"))
      (node (ref "R57") (pin "1") (pinfunction "1_1") (pintype "passive"))
      (node (ref "U5") (pin "174") (pinfunction "nTRST_174") (pintype "input"))
    )
    (net (code "125") (name "/nWAIT") (class "Default")
      (node (ref "U5") (pin "144") (pinfunction "INT5/DREQ1/nWAIT_144") (pintype "input"))
    )
    (net (code "126") (name "/nWE") (class "Default")
      (node (ref "U5") (pin "39") (pinfunction "nWE_39") (pintype "output"))
    )
    (net (code "129") (name "GND") (class "Default")
      (node (ref "C100") (pin "2") (pinfunction "2_2") (pintype "passive"))
      (node (ref "C101") (pin "2") (pinfunction "2_2") (pintype "passive"))
      (node (ref "C62") (pin "2") (pinfunction "2_2") (pintype "passive"))
      (node (ref "C66") (pin "2") (pinfunction "2_2") (pintype "passive"))
      (node (ref "C67") (pin "2") (pinfunction "2_2") (pintype "passive"))
      (node (ref "C68") (pin "2") (pinfunction "2_2") (pintype "passive"))
      (node (ref "C69") (pin "2") (pinfunction "2_2") (pintype "passive"))
      (node (ref "C70") (pin "2") (pinfunction "2_2") (pintype "passive"))
      (node (ref "C71") (pin "2") (pinfunction "2_2") (pintype "passive"))
      (node (ref "C72") (pin "2") (pinfunction "2_2") (pintype "passive"))
      (node (ref "C73") (pin "2") (pinfunction "2_2") (pintype "passive"))
      (node (ref "C74") (pin "2") (pinfunction "2_2") (pintype "passive"))
      (node (ref "C75") (pin "2") (pinfunction "2_2") (pintype "passive"))
      (node (ref "C76") (pin "2") (pinfunction "2_2") (pintype "passive"))
      (node (ref "C77") (pin "2") (pinfunction "2_2") (pintype "passive"))
      (node (ref "C78") (pin "2") (pinfunction "2_2") (pintype "passive"))
      (node (ref "C79") (pin "2") (pinfunction "2_2") (pintype "passive"))
      (node (ref "C80") (pin "2") (pinfunction "2_2") (pintype "passive"))
      (node (ref "C81") (pin "2") (pinfunction "2_2") (pintype "passive"))
      (node (ref "C82") (pin "2") (pinfunction "2_2") (pintype "passive"))
      (node (ref "C83") (pin "2") (pinfunction "2_2") (pintype "passive"))
      (node (ref "C84") (pin "2") (pinfunction "2_2") (pintype "passive"))
      (node (ref "C85") (pin "2") (pinfunction "2_2") (pintype "passive"))
      (node (ref "C86") (pin "2") (pinfunction "2_2") (pintype "passive"))
      (node (ref "C87") (pin "2") (pinfunction "2_2") (pintype "passive"))
      (node (ref "C88") (pin "2") (pinfunction "2_2") (pintype "passive"))
      (node (ref "C89") (pin "2") (pinfunction "2_2") (pintype "passive"))
      (node (ref "C90") (pin "2") (pinfunction "2_2") (pintype "passive"))
      (node (ref "C91") (pin "2") (pinfunction "2_2") (pintype "passive"))
      (node (ref "C92") (pin "2") (pinfunction "2_2") (pintype "passive"))
      (node (ref "C93") (pin "2") (pinfunction "2_2") (pintype "passive"))
      (node (ref "C94") (pin "2") (pinfunction "2_2") (pintype "passive"))
      (node (ref "C95") (pin "2") (pinfunction "2_2") (pintype "passive"))
      (node (ref "C96") (pin "2") (pinfunction "2_2") (pintype "passive"))
      (node (ref "C97") (pin "2") (pinfunction "2_2") (pintype "passive"))
      (node (ref "C98") (pin "2") (pinfunction "2_2") (pintype "passive"))
      (node (ref "C99") (pin "2") (pinfunction "2_2") (pintype "passive"))
      (node (ref "LED3") (pin "2") (pinfunction "K_2") (pintype "passive"))
      (node (ref "P2") (pin "10") (pinfunction "10_10") (pintype "passive"))
      (node (ref "P2") (pin "11") (pinfunction "11_11") (pintype "passive"))
      (node (ref "P2") (pin "12") (pinfunction "12_12") (pintype "passive"))
      (node (ref "P2") (pin "14") (pinfunction "14_14") (pintype "passive"))
      (node (ref "P2") (pin "16") (pinfunction "16_16") (pintype "passive"))
      (node (ref "P2") (pin "18") (pinfunction "18_18") (pintype "passive"))
      (node (ref "P2") (pin "20") (pinfunction "20_20") (pintype "passive"))
      (node (ref "P2") (pin "4") (pinfunction "4_4") (pintype "passive"))
      (node (ref "P2") (pin "6") (pinfunction "6_6") (pintype "passive"))
      (node (ref "P2") (pin "8") (pinfunction "8_8") (pintype "passive"))
      (node (ref "P5") (pin "1") (pinfunction "1_1") (pintype "passive"))
      (node (ref "R37") (pin "1") (pinfunction "1_1") (pintype "passive"))
      (node (ref "R46") (pin "1") (pinfunction "1_1") (pintype "passive"))
      (node (ref "R60") (pin "2") (pinfunction "2_2") (pintype "passive"))
      (node (ref "R63") (pin "1") (pinfunction "1_1") (pintype "passive"))
      (node (ref "R66") (pin "1") (pinfunction "1_1") (pintype "passive"))
      (node (ref "U5") (pin "103") (pinfunction "VSS_103") (pintype "power_in"))
      (node (ref "U5") (pin "120") (pinfunction "VSSC_120") (pintype "power_in"))
      (node (ref "U5") (pin "128") (pinfunction "VSS_128") (pintype "power_in"))
      (node (ref "U5") (pin "13") (pinfunction "VSS_13") (pintype "power_in"))
      (node (ref "U5") (pin "138") (pinfunction "VSSC_138") (pintype "power_in"))
      (node (ref "U5") (pin "149") (pinfunction "VSS_149") (pintype "power_in"))
      (node (ref "U5") (pin "158") (pinfunction "VSSC_158") (pintype "power_in"))
      (node (ref "U5") (pin "168") (pinfunction "VSS_168") (pintype "power_in"))
      (node (ref "U5") (pin "175") (pinfunction "TEST1_175") (pintype "input"))
      (node (ref "U5") (pin "23") (pinfunction "VSS_23") (pintype "power_in"))
      (node (ref "U5") (pin "33") (pinfunction "VSS_33") (pintype "power_in"))
      (node (ref "U5") (pin "45") (pinfunction "VSSC_45") (pintype "power_in"))
      (node (ref "U5") (pin "55") (pinfunction "VSS_55") (pintype "power_in"))
      (node (ref "U5") (pin "70") (pinfunction "VSS_70") (pintype "power_in"))
      (node (ref "U5") (pin "80") (pinfunction "VSS_80") (pintype "power_in"))
      (node (ref "U5") (pin "88") (pinfunction "CLKINSEL_88") (pintype "input"))
      (node (ref "U6") (pin "15") (pinfunction "~{STB}_15") (pintype "input"))
      (node (ref "U6") (pin "8") (pinfunction "GND_8") (pintype "power_in"))
    )
    (net (code "130") (name "Net-(C59-Pad1)") (class "Default")
      (node (ref "C59") (pin "1") (pinfunction "1_1") (pintype "passive"))
      (node (ref "R36") (pin "1") (pinfunction "1_1") (pintype "passive"))
      (node (ref "R37") (pin "2") (pinfunction "2_2") (pintype "passive"))
    )
    (net (code "131") (name "Net-(C60-Pad1)") (class "Default")
      (node (ref "C60") (pin "1") (pinfunction "1_1") (pintype "passive"))
      (node (ref "R44") (pin "1") (pinfunction "1_1") (pintype "passive"))
      (node (ref "R46") (pin "2") (pinfunction "2_2") (pintype "passive"))
    )
    (net (code "132") (name "Net-(D1-k)") (class "Default")
      (node (ref "C61") (pin "1") (pinfunction "1_1") (pintype "passive"))
      (node (ref "C63") (pin "1") (pinfunction "1_1") (pintype "passive"))
      (node (ref "C64") (pin "1") (pinfunction "1_1") (pintype "passive"))
      (node (ref "C65") (pin "1") (pinfunction "1_1") (pintype "passive"))
      (node (ref "D1") (pin "3") (pinfunction "k_3") (pintype "passive"))
      (node (ref "R59") (pin "2") (pinfunction "2_2") (pintype "passive"))
      (node (ref "U5") (pin "91") (pinfunction "VDDA_91") (pintype "power_in"))
    )
    (net (code "133") (name "Net-(LED3-A)") (class "Default")
      (node (ref "LED3") (pin "1") (pinfunction "A_1") (pintype "passive"))
      (node (ref "R58") (pin "2") (pinfunction "2_2") (pintype "passive"))
    )
    (net (code "134") (name "Net-(P2-Pad17)") (class "Default")
      (node (ref "P2") (pin "17") (pinfunction "17_17") (pintype "passive"))
      (node (ref "R66") (pin "2") (pinfunction "2_2") (pintype "passive"))
    )
    (net (code "135") (name "Net-(P2-Pad19)") (class "Default")
      (node (ref "P2") (pin "19") (pinfunction "19_19") (pintype "passive"))
      (node (ref "R67") (pin "2") (pinfunction "2_2") (pintype "passive"))
    )
    (net (code "136") (name "Net-(U5A-CLKIN{slash}UARTCLK)") (class "Default")
      (node (ref "R23") (pin "1") (pinfunction "1_1") (pintype "passive"))
      (node (ref "U5") (pin "98") (pinfunction "CLKIN/UARTCLK_98") (pintype "input"))
    )
    (net (code "137") (name "Net-(U5A-INT6{slash}LCDVD10)") (class "Default")
      (node (ref "R35") (pin "1") (pinfunction "1_1") (pintype "passive"))
      (node (ref "U5") (pin "115") (pinfunction "INT6/LCDVD10_115") (pintype "bidirectional"))
    )
    (net (code "138") (name "Net-(U5A-LCDVD0)") (class "Default")
      (node (ref "R25") (pin "1") (pinfunction "1_1") (pintype "passive"))
      (node (ref "U5") (pin "127") (pinfunction "LCDVD0_127") (pintype "output"))
    )
    (net (code "139") (name "Net-(U5A-LCDVD1)") (class "Default")
      (node (ref "R26") (pin "1") (pinfunction "1_1") (pintype "passive"))
      (node (ref "U5") (pin "126") (pinfunction "LCDVD1_126") (pintype "output"))
    )
    (net (code "140") (name "Net-(U5A-PA3{slash}UARTRX1)") (class "Default")
      (node (ref "R55") (pin "1") (pinfunction "1_1") (pintype "passive"))
      (node (ref "U5") (pin "160") (pinfunction "PA3/UARTRX1_160") (pintype "bidirectional"))
    )
    (net (code "141") (name "Net-(U5A-PA4{slash}UARTTX1)") (class "Default")
      (node (ref "R54") (pin "1") (pinfunction "1_1") (pintype "passive"))
      (node (ref "U5") (pin "159") (pinfunction "PA4/UARTTX1_159") (pintype "bidirectional"))
    )
    (net (code "142") (name "Net-(U5A-PB4{slash}LCDVD12{slash}LCDREV)") (class "Default")
      (node (ref "R53") (pin "1") (pinfunction "1_1") (pintype "passive"))
      (node (ref "U5") (pin "142") (pinfunction "PB4/LCDVD12/LCDREV_142") (pintype "bidirectional"))
    )
    (net (code "143") (name "Net-(U5A-PB5{slash}LCDVD13)") (class "Default")
      (node (ref "R52") (pin "1") (pinfunction "1_1") (pintype "passive"))
      (node (ref "U5") (pin "141") (pinfunction "PB5/LCDVD13_141") (pintype "bidirectional"))
    )
    (net (code "144") (name "Net-(U5A-PB6{slash}LCDVD14)") (class "Default")
      (node (ref "R51") (pin "1") (pinfunction "1_1") (pintype "passive"))
      (node (ref "U5") (pin "140") (pinfunction "PB6/LCDVD14_140") (pintype "bidirectional"))
    )
    (net (code "145") (name "Net-(U5A-PB7{slash}LCDVD15)") (class "Default")
      (node (ref "R50") (pin "1") (pinfunction "1_1") (pintype "passive"))
      (node (ref "U5") (pin "139") (pinfunction "PB7/LCDVD15_139") (pintype "bidirectional"))
    )
    (net (code "146") (name "Net-(U5A-PC0{slash}LCDENAB{slash}LCDSPL)") (class "Default")
      (node (ref "R45") (pin "1") (pinfunction "1_1") (pintype "passive"))
      (node (ref "U5") (pin "137") (pinfunction "PC0/LCDENAB/LCDSPL_137") (pintype "bidirectional"))
    )
    (net (code "147") (name "Net-(U5A-PC1{slash}LCDVDDEN{slash}LCDCLS)") (class "Default")
      (node (ref "R43") (pin "1") (pinfunction "1_1") (pintype "passive"))
      (node (ref "U5") (pin "135") (pinfunction "PC1/LCDVDDEN/LCDCLS_135") (pintype "bidirectional"))
    )
    (net (code "148") (name "Net-(U5A-PC2{slash}LCDDCLKIN)") (class "Default")
      (node (ref "R42") (pin "1") (pinfunction "1_1") (pintype "passive"))
      (node (ref "U5") (pin "134") (pinfunction "PC2/LCDDCLKIN_134") (pintype "bidirectional"))
    )
    (net (code "149") (name "Net-(U5A-PC3{slash}LCDDCLK)") (class "Default")
      (node (ref "R41") (pin "1") (pinfunction "1_1") (pintype "passive"))
      (node (ref "U5") (pin "133") (pinfunction "PC3/LCDDCLK_133") (pintype "bidirectional"))
    )
    (net (code "150") (name "Net-(U5A-PC4{slash}LCDVD16)") (class "Default")
      (node (ref "R49") (pin "1") (pinfunction "1_1") (pintype "passive"))
      (node (ref "U5") (pin "132") (pinfunction "PC4/LCDVD16_132") (pintype "bidirectional"))
    )
    (net (code "151") (name "Net-(U5A-PC5{slash}LCDLP)") (class "Default")
      (node (ref "R40") (pin "1") (pinfunction "1_1") (pintype "passive"))
      (node (ref "U5") (pin "131") (pinfunction "PC5/LCDLP_131") (pintype "bidirectional"))
    )
    (net (code "152") (name "Net-(U5A-PC6{slash}LCDVD17)") (class "Default")
      (node (ref "R48") (pin "1") (pinfunction "1_1") (pintype "passive"))
      (node (ref "U5") (pin "130") (pinfunction "PC6/LCDVD17_130") (pintype "bidirectional"))
    )
    (net (code "153") (name "Net-(U5A-PC7{slash}LCDFP{slash}LCDSPS)") (class "Default")
      (node (ref "R39") (pin "1") (pinfunction "1_1") (pintype "passive"))
      (node (ref "U5") (pin "129") (pinfunction "PC7/LCDFP/LCDSPS_129") (pintype "bidirectional"))
    )
    (net (code "154") (name "Net-(U5A-PD0{slash}LCDVD2)") (class "Default")
      (node (ref "R27") (pin "1") (pinfunction "1_1") (pintype "passive"))
      (node (ref "U5") (pin "124") (pinfunction "PD0/LCDVD2_124") (pintype "bidirectional"))
    )
    (net (code "155") (name "Net-(U5A-PD1{slash}LCDVD3)") (class "Default")
      (node (ref "R28") (pin "1") (pinfunction "1_1") (pintype "passive"))
      (node (ref "U5") (pin "123") (pinfunction "PD1/LCDVD3_123") (pintype "bidirectional"))
    )
    (net (code "156") (name "Net-(U5A-PD2{slash}LCDVD4)") (class "Default")
      (node (ref "R29") (pin "1") (pinfunction "1_1") (pintype "passive"))
      (node (ref "U5") (pin "122") (pinfunction "PD2/LCDVD4_122") (pintype "bidirectional"))
    )
    (net (code "157") (name "Net-(U5A-PD3{slash}LCDVD5)") (class "Default")
      (node (ref "R30") (pin "1") (pinfunction "1_1") (pintype "passive"))
      (node (ref "U5") (pin "121") (pinfunction "PD3/LCDVD5_121") (pintype "bidirectional"))
    )
    (net (code "158") (name "Net-(U5A-PD4{slash}LCDVD6{slash}LCDPS)") (class "Default")
      (node (ref "R31") (pin "1") (pinfunction "1_1") (pintype "passive"))
      (node (ref "U5") (pin "119") (pinfunction "PD4/LCDVD6/LCDPS_119") (pintype "bidirectional"))
    )
    (net (code "159") (name "Net-(U5A-PD5{slash}LCDVD7)") (class "Default")
      (node (ref "R32") (pin "1") (pinfunction "1_1") (pintype "passive"))
      (node (ref "U5") (pin "118") (pinfunction "PD5/LCDVD7_118") (pintype "bidirectional"))
    )
    (net (code "160") (name "Net-(U5A-PD6{slash}LCDVD8)") (class "Default")
      (node (ref "R33") (pin "1") (pinfunction "1_1") (pintype "passive"))
      (node (ref "U5") (pin "117") (pinfunction "PD6/LCDVD8_117") (pintype "bidirectional"))
    )
    (net (code "161") (name "Net-(U5A-PD7{slash}LCDVD9)") (class "Default")
      (node (ref "R34") (pin "1") (pinfunction "1_1") (pintype "passive"))
      (node (ref "U5") (pin "116") (pinfunction "PD7/LCDVD9_116") (pintype "bidirectional"))
    )
    (net (code "162") (name "Net-(U5A-PE6{slash}nDCS1)") (class "Default")
      (node (ref "R21") (pin "1") (pinfunction "1_1") (pintype "passive"))
      (node (ref "U5") (pin "104") (pinfunction "PE6/nDCS1_104") (pintype "bidirectional"))
    )
    (net (code "163") (name "Net-(U5A-PF1{slash}CLKEN)") (class "Default")
      (node (ref "R22") (pin "1") (pinfunction "1_1") (pintype "passive"))
      (node (ref "U5") (pin "99") (pinfunction "PF1/CLKEN_99") (pintype "bidirectional"))
    )
    (net (code "164") (name "Net-(U5A-UARTIRRX0{slash}UARTRX0)") (class "Default")
      (node (ref "R56") (pin "1") (pinfunction "1_1") (pintype "passive"))
      (node (ref "U5") (pin "163") (pinfunction "UARTIRRX0/UARTRX0_163") (pintype "input"))
    )
    (net (code "165") (name "Net-(U5B-VSSA)") (class "Default")
      (node (ref "C61") (pin "2") (pinfunction "2_2") (pintype "passive"))
      (node (ref "C63") (pin "2") (pinfunction "2_2") (pintype "passive"))
      (node (ref "C64") (pin "2") (pinfunction "2_2") (pintype "passive"))
      (node (ref "C65") (pin "2") (pinfunction "2_2") (pintype "passive"))
      (node (ref "U5") (pin "92") (pinfunction "VSSA_92") (pintype "power_in"))
    )
    (net (code "166") (name "Net-(U6-SEL)") (class "Default")
      (node (ref "P1") (pin "1") (pinfunction "1_1") (pintype "passive"))
      (node (ref "P5") (pin "2") (pinfunction "2_2") (pintype "passive"))
      (node (ref "R58") (pin "1") (pinfunction "1_1") (pintype "passive"))
      (node (ref "R60") (pin "1") (pinfunction "1_1") (pintype "passive"))
      (node (ref "U6") (pin "1") (pinfunction "SEL_1") (pintype "input"))
    )
    (net (code "167") (name "VCC1V8") (class "Default")
      (node (ref "C100") (pin "1") (pinfunction "1_1") (pintype "passive"))
      (node (ref "C101") (pin "1") (pinfunction "1_1") (pintype "passive"))
      (node (ref "C88") (pin "1") (pinfunction "1_1") (pintype "passive"))
      (node (ref "C89") (pin "1") (pinfunction "1_1") (pintype "passive"))
      (node (ref "C90") (pin "1") (pinfunction "1_1") (pintype "passive"))
      (node (ref "C91") (pin "1") (pinfunction "1_1") (pintype "passive"))
      (node (ref "C92") (pin "1") (pinfunction "1_1") (pintype "passive"))
      (node (ref "C93") (pin "1") (pinfunction "1_1") (pintype "passive"))
      (node (ref "C94") (pin "1") (pinfunction "1_1") (pintype "passive"))
      (node (ref "C95") (pin "1") (pinfunction "1_1") (pintype "passive"))
      (node (ref "C96") (pin "1") (pinfunction "1_1") (pintype "passive"))
      (node (ref "C97") (pin "1") (pinfunction "1_1") (pintype "passive"))
      (node (ref "C98") (pin "1") (pinfunction "1_1") (pintype "passive"))
      (node (ref "C99") (pin "1") (pinfunction "1_1") (pintype "passive"))
      (node (ref "D1") (pin "1") (pinfunction "A_1") (pintype "passive"))
      (node (ref "R59") (pin "1") (pinfunction "1_1") (pintype "passive"))
      (node (ref "U5") (pin "113") (pinfunction "VDDC_113") (pintype "power_in"))
      (node (ref "U5") (pin "136") (pinfunction "VDDC_136") (pintype "power_in"))
      (node (ref "U5") (pin "154") (pinfunction "VDDC_154") (pintype "power_in"))
      (node (ref "U5") (pin "40") (pinfunction "VDDC_40") (pintype "power_in"))
      (node (ref "U5") (pin "75") (pinfunction "VDDC_75") (pintype "power_in"))
      (node (ref "U5") (pin "95") (pinfunction "VDDC_95") (pintype "power_in"))
    )
    (net (code "168") (name "VCC3V3") (class "Default")
      (node (ref "C62") (pin "1") (pinfunction "1_1") (pintype "passive"))
      (node (ref "C66") (pin "1") (pinfunction "1_1") (pintype "passive"))
      (node (ref "C67") (pin "1") (pinfunction "1_1") (pintype "passive"))
      (node (ref "C68") (pin "1") (pinfunction "1_1") (pintype "passive"))
      (node (ref "C69") (pin "1") (pinfunction "1_1") (pintype "passive"))
      (node (ref "C70") (pin "1") (pinfunction "1_1") (pintype "passive"))
      (node (ref "C71") (pin "1") (pinfunction "1_1") (pintype "passive"))
      (node (ref "C72") (pin "1") (pinfunction "1_1") (pintype "passive"))
      (node (ref "C73") (pin "1") (pinfunction "1_1") (pintype "passive"))
      (node (ref "C74") (pin "1") (pinfunction "1_1") (pintype "passive"))
      (node (ref "C75") (pin "1") (pinfunction "1_1") (pintype "passive"))
      (node (ref "C76") (pin "1") (pinfunction "1_1") (pintype "passive"))
      (node (ref "C77") (pin "1") (pinfunction "1_1") (pintype "passive"))
      (node (ref "C78") (pin "1") (pinfunction "1_1") (pintype "passive"))
      (node (ref "C79") (pin "1") (pinfunction "1_1") (pintype "passive"))
      (node (ref "C80") (pin "1") (pinfunction "1_1") (pintype "passive"))
      (node (ref "C81") (pin "1") (pinfunction "1_1") (pintype "passive"))
      (node (ref "C82") (pin "1") (pinfunction "1_1") (pintype "passive"))
      (node (ref "C83") (pin "1") (pinfunction "1_1") (pintype "passive"))
      (node (ref "C84") (pin "1") (pinfunction "1_1") (pintype "passive"))
      (node (ref "C85") (pin "1") (pinfunction "1_1") (pintype "passive"))
      (node (ref "C86") (pin "1") (pinfunction "1_1") (pintype "passive"))
      (node (ref "C87") (pin "1") (pinfunction "1_1") (pintype "passive"))
      (node (ref "P1") (pin "2") (pinfunction "2_2") (pintype "passive"))
      (node (ref "P2") (pin "1") (pinfunction "1_1") (pintype "passive"))
      (node (ref "P2") (pin "2") (pinfunction "2_2") (pintype "passive"))
      (node (ref "P5") (pin "3") (pinfunction "3_3") (pintype "passive"))
      (node (ref "R20") (pin "2") (pinfunction "2_2") (pintype "passive"))
      (node (ref "R21") (pin "2") (pinfunction "2_2") (pintype "passive"))
      (node (ref "R22") (pin "2") (pinfunction "2_2") (pintype "passive"))
      (node (ref "R23") (pin "2") (pinfunction "2_2") (pintype "passive"))
      (node (ref "R24") (pin "2") (pinfunction "2_2") (pintype "passive"))
      (node (ref "R25") (pin "2") (pinfunction "2_2") (pintype "passive"))
      (node (ref "R26") (pin "2") (pinfunction "2_2") (pintype "passive"))
      (node (ref "R27") (pin "2") (pinfunction "2_2") (pintype "passive"))
      (node (ref "R28") (pin "2") (pinfunction "2_2") (pintype "passive"))
      (node (ref "R29") (pin "2") (pinfunction "2_2") (pintype "passive"))
      (node (ref "R30") (pin "2") (pinfunction "2_2") (pintype "passive"))
      (node (ref "R31") (pin "2") (pinfunction "2_2") (pintype "passive"))
      (node (ref "R32") (pin "2") (pinfunction "2_2") (pintype "passive"))
      (node (ref "R33") (pin "2") (pinfunction "2_2") (pintype "passive"))
      (node (ref "R34") (pin "2") (pinfunction "2_2") (pintype "passive"))
      (node (ref "R35") (pin "2") (pinfunction "2_2") (pintype "passive"))
      (node (ref "R39") (pin "2") (pinfunction "2_2") (pintype "passive"))
      (node (ref "R40") (pin "2") (pinfunction "2_2") (pintype "passive"))
      (node (ref "R41") (pin "2") (pinfunction "2_2") (pintype "passive"))
      (node (ref "R42") (pin "2") (pinfunction "2_2") (pintype "passive"))
      (node (ref "R43") (pin "2") (pinfunction "2_2") (pintype "passive"))
      (node (ref "R45") (pin "2") (pinfunction "2_2") (pintype "passive"))
      (node (ref "R48") (pin "2") (pinfunction "2_2") (pintype "passive"))
      (node (ref "R49") (pin "2") (pinfunction "2_2") (pintype "passive"))
      (node (ref "R50") (pin "2") (pinfunction "2_2") (pintype "passive"))
      (node (ref "R51") (pin "2") (pinfunction "2_2") (pintype "passive"))
      (node (ref "R52") (pin "2") (pinfunction "2_2") (pintype "passive"))
      (node (ref "R53") (pin "2") (pinfunction "2_2") (pintype "passive"))
      (node (ref "R54") (pin "2") (pinfunction "2_2") (pintype "passive"))
      (node (ref "R55") (pin "2") (pinfunction "2_2") (pintype "passive"))
      (node (ref "R56") (pin "2") (pinfunction "2_2") (pintype "passive"))
      (node (ref "R57") (pin "2") (pinfunction "2_2") (pintype "passive"))
      (node (ref "R61") (pin "1") (pinfunction "1_1") (pintype "passive"))
      (node (ref "R62") (pin "1") (pinfunction "1_1") (pintype "passive"))
      (node (ref "R67") (pin "1") (pinfunction "1_1") (pintype "passive"))
      (node (ref "U5") (pin "1") (pinfunction "nTSTA_1") (pintype "input"))
      (node (ref "U5") (pin "100") (pinfunction "VDD_100") (pintype "power_in"))
      (node (ref "U5") (pin "125") (pinfunction "VDD_125") (pintype "power_in"))
      (node (ref "U5") (pin "143") (pinfunction "VDD_143") (pintype "power_in"))
      (node (ref "U5") (pin "161") (pinfunction "VDD_161") (pintype "power_in"))
      (node (ref "U5") (pin "176") (pinfunction "TEST2_176") (pintype "input"))
      (node (ref "U5") (pin "18") (pinfunction "VDD_18") (pintype "power_in"))
      (node (ref "U5") (pin "28") (pinfunction "VDD_28") (pintype "power_in"))
      (node (ref "U5") (pin "49") (pinfunction "VDD_49") (pintype "power_in"))
      (node (ref "U5") (pin "64") (pinfunction "VDD_64") (pintype "power_in"))
      (node (ref "U5") (pin "8") (pinfunction "VDD_8") (pintype "power_in"))
      (node (ref "U5") (pin "85") (pinfunction "VDD_85") (pintype "power_in"))
      (node (ref "U6") (pin "16") (pinfunction "VDD_16") (pintype "power_in"))
    )
    (net (code "169") (name "unconnected-(D1-Pad2)") (class "Default")
      (node (ref "D1") (pin "2") (pintype "passive"))
    )
    (net (code "170") (name "unconnected-(U5A-CTOUT1B{slash}DACK1-Pad145)") (class "Default")
      (node (ref "U5") (pin "145") (pinfunction "CTOUT1B/DACK1_145") (pintype "output+no_connect"))
    )
    (net (code "171") (name "unconnected-(U5A-PWM1{slash}DEOT1-Pad157)") (class "Default")
      (node (ref "U5") (pin "157") (pinfunction "PWM1/DEOT1_157") (pintype "output+no_connect"))
    )
    (net (code "172") (name "unconnected-(U5A-UARTIRTX0{slash}UARTTX0-Pad162)") (class "Default")
      (node (ref "U5") (pin "162") (pinfunction "UARTIRTX0/UARTTX0_162") (pintype "output"))
    )
  )
)
